# GCM_SCH.net
KiCad netlist of a schematic drawn in Altium Designer
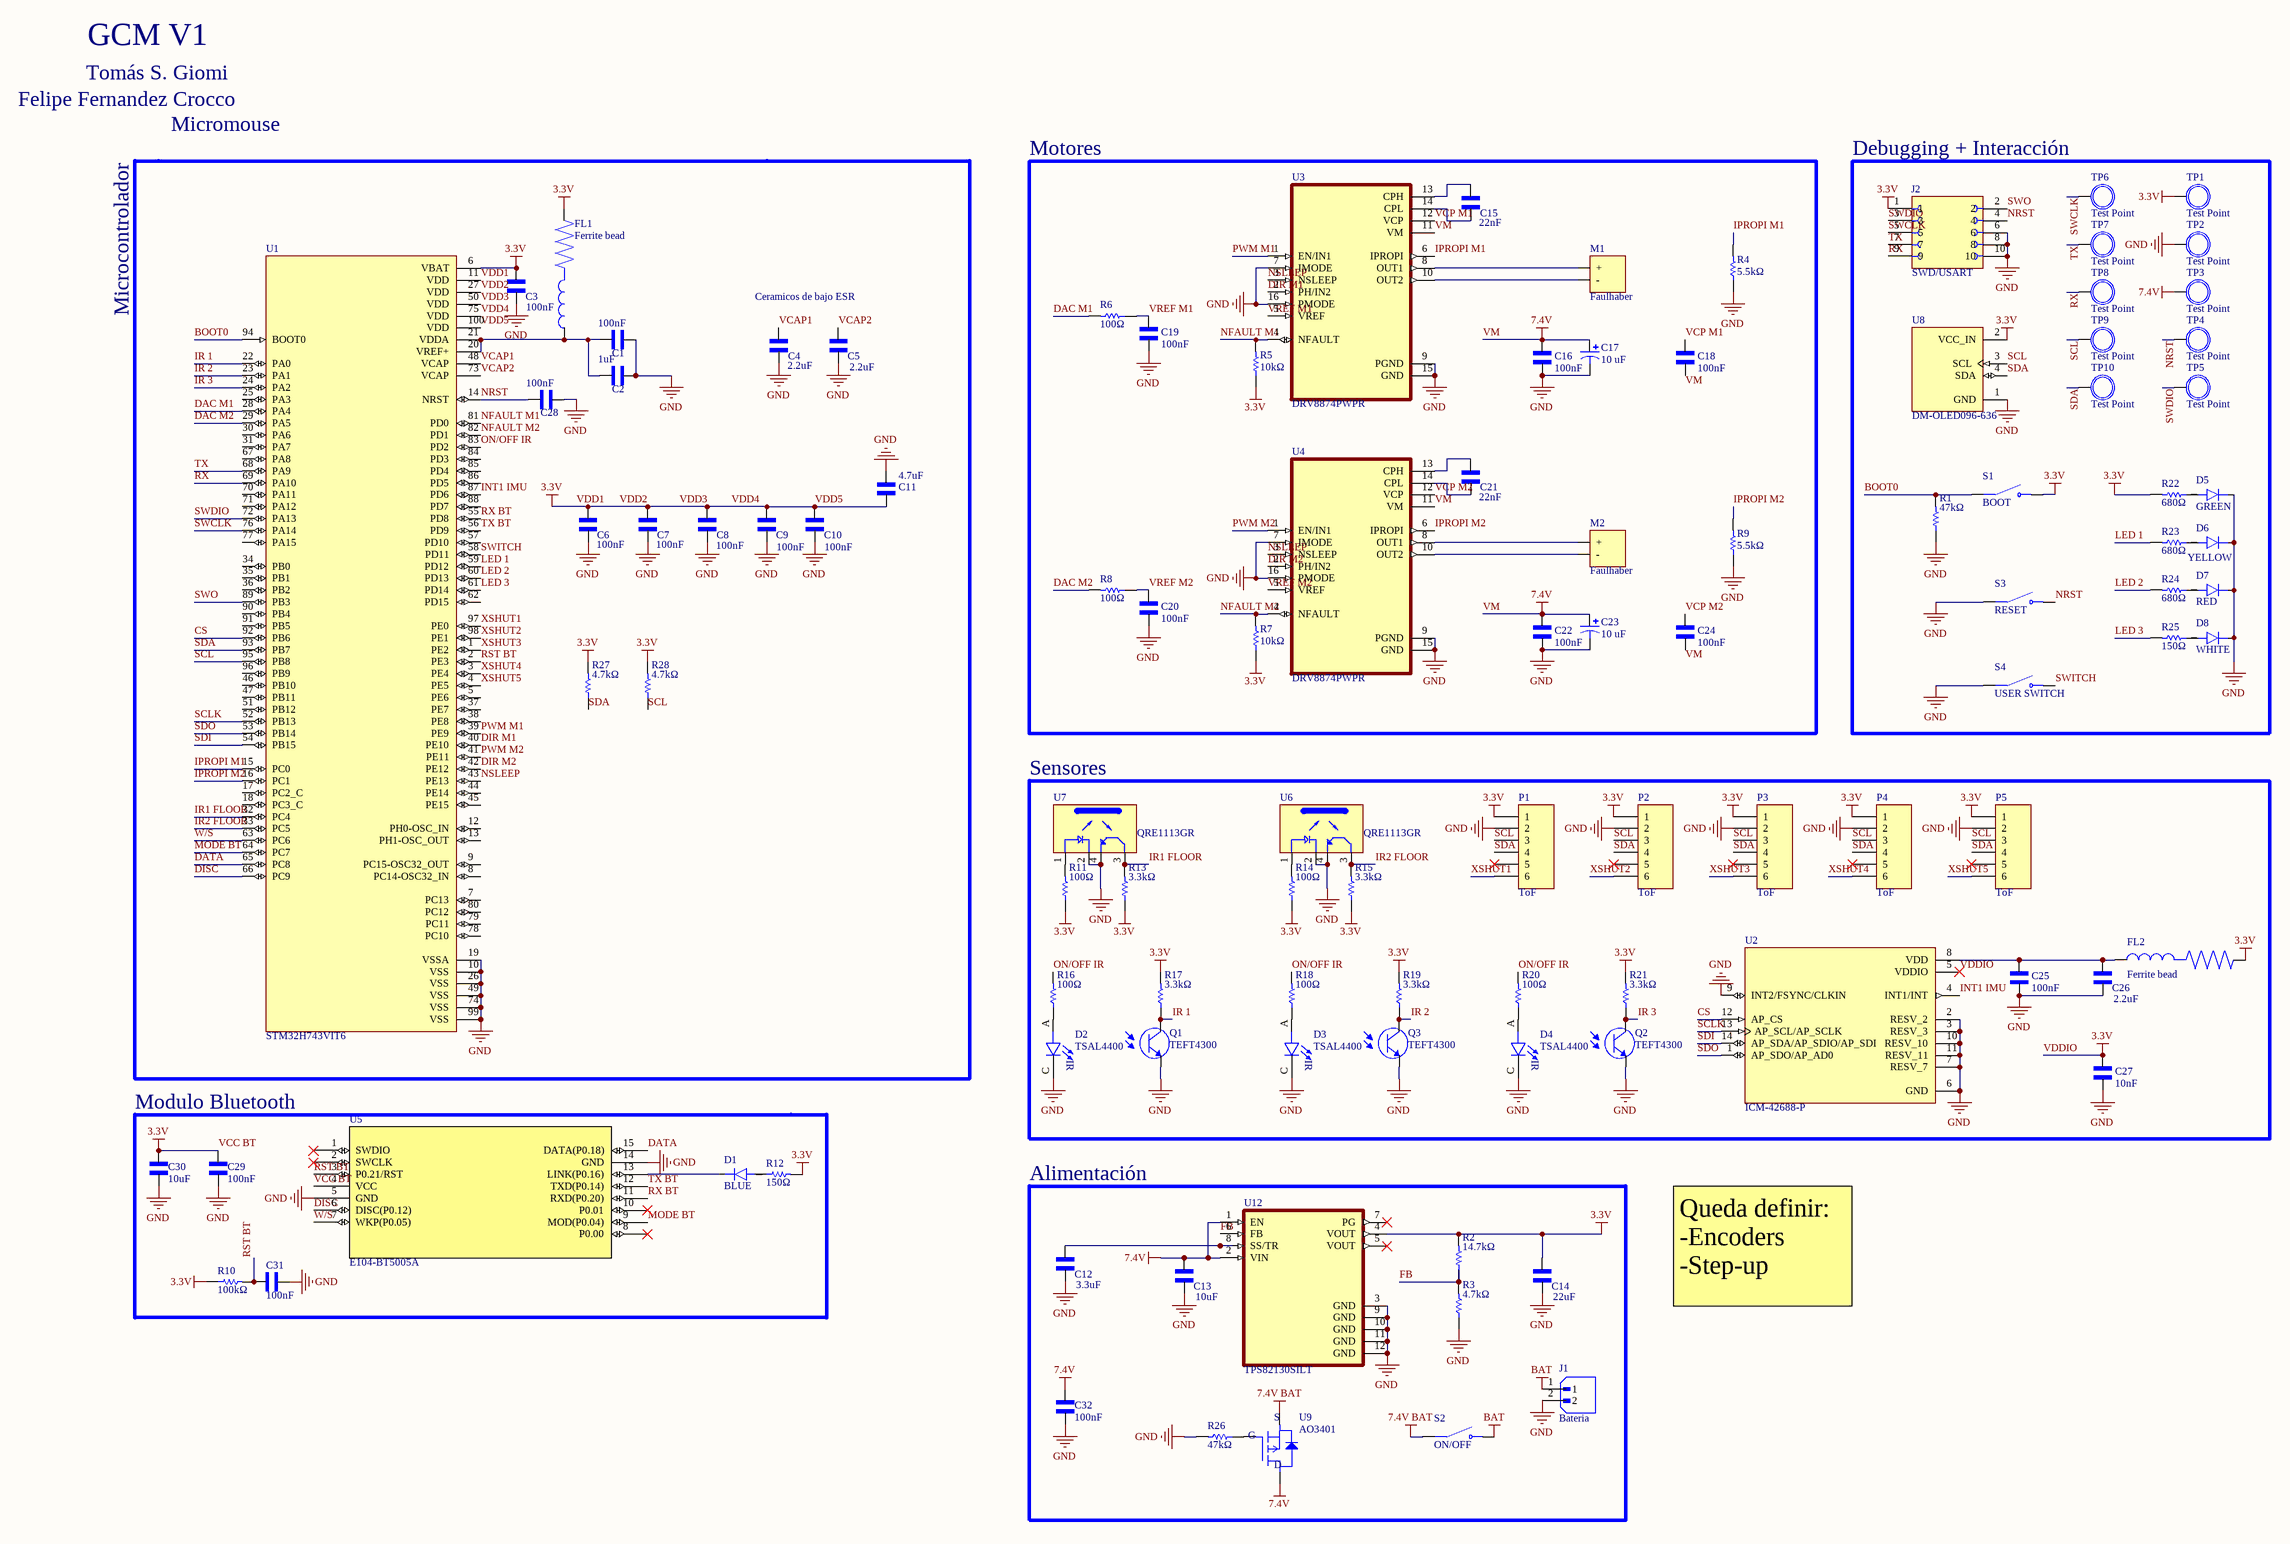
[diagram p0: GCM_SCH.SchDoc]

(export (version "E")
  (design (tool "Eeschema 10.0.6"))
  (components
    (comp (ref "C1")
      (value "100nF")
      (footprint "CAPACITOR TANTALIO")
      (description "0805")
      (fields (field (name "MP") "GRM035R60J475ME15D") (field (name "MF") "Murata"))
      (libsource (lib "") (part "CAPACITOR TANTALIO_1"))
    )
    (comp (ref "C2")
      (value "1uF")
      (footprint "CAPACITOR TANTALIO")
      (description "0805")
      (fields (field (name "MP") "GRM035R60J475ME15D") (field (name "MF") "Murata"))
      (libsource (lib "") (part "CAPACITOR TANTALIO_1"))
    )
    (comp (ref "C3")
      (value "100nF")
      (footprint "CAPACITOR TANTALIO")
      (description "0805")
      (fields (field (name "MP") "GRM035R60J475ME15D") (field (name "MF") "Murata"))
      (libsource (lib "GCMLibreriasSCH") (part "CAPACITOR TANTALIO"))
    )
    (comp (ref "C4")
      (value "2.2uF")
      (footprint "CAPACITOR TANTALIO")
      (description "0805")
      (fields (field (name "MP") "GRM035R60J475ME15D") (field (name "MF") "Murata"))
      (libsource (lib "GCMLibreriasSCH") (part "CAPACITOR TANTALIO"))
    )
    (comp (ref "C5")
      (value "2.2uF")
      (footprint "CAPACITOR TANTALIO")
      (description "0805")
      (fields (field (name "MP") "GRM035R60J475ME15D") (field (name "MF") "Murata"))
      (libsource (lib "GCMLibreriasSCH") (part "CAPACITOR TANTALIO"))
    )
    (comp (ref "C6")
      (value "100nF")
      (footprint "CAPACITOR TANTALIO")
      (description "0805")
      (fields (field (name "MP") "GRM035R60J475ME15D") (field (name "MF") "Murata"))
      (libsource (lib "GCMLibreriasSCH") (part "CAPACITOR TANTALIO"))
    )
    (comp (ref "C7")
      (value "100nF")
      (footprint "CAPACITOR TANTALIO")
      (description "0805")
      (fields (field (name "MP") "GRM035R60J475ME15D") (field (name "MF") "Murata"))
      (libsource (lib "GCMLibreriasSCH") (part "CAPACITOR TANTALIO"))
    )
    (comp (ref "C8")
      (value "100nF")
      (footprint "CAPACITOR TANTALIO")
      (description "0805")
      (fields (field (name "MP") "GRM035R60J475ME15D") (field (name "MF") "Murata"))
      (libsource (lib "GCMLibreriasSCH") (part "CAPACITOR TANTALIO"))
    )
    (comp (ref "C9")
      (value "100nF")
      (footprint "CAPACITOR TANTALIO")
      (description "0805")
      (fields (field (name "MP") "GRM035R60J475ME15D") (field (name "MF") "Murata"))
      (libsource (lib "GCMLibreriasSCH") (part "CAPACITOR TANTALIO"))
    )
    (comp (ref "C10")
      (value "100nF")
      (footprint "CAPACITOR TANTALIO")
      (description "0805")
      (fields (field (name "MP") "GRM035R60J475ME15D") (field (name "MF") "Murata"))
      (libsource (lib "GCMLibreriasSCH") (part "CAPACITOR TANTALIO"))
    )
    (comp (ref "C11")
      (value "4.7uF")
      (footprint "CAPACITOR TANTALIO")
      (description "0805")
      (fields (field (name "MP") "GRM035R60J475ME15D") (field (name "MF") "Murata"))
      (libsource (lib "GCMLibreriasSCH") (part "CAPACITOR TANTALIO"))
    )
    (comp (ref "C12")
      (value "3.3uF")
      (footprint "CAPACITOR TANTALIO")
      (description "0805")
      (fields (field (name "MP") "GRM035R60J475ME15D") (field (name "MF") "Murata"))
      (libsource (lib "GCMLibreriasSCH") (part "CAPACITOR TANTALIO"))
    )
    (comp (ref "C13")
      (value "10uF")
      (footprint "CAPACITOR TANTALIO")
      (description "0805")
      (fields (field (name "MP") "GRM035R60J475ME15D") (field (name "MF") "Murata"))
      (libsource (lib "GCMLibreriasSCH") (part "CAPACITOR TANTALIO"))
    )
    (comp (ref "C14")
      (value "22uF")
      (footprint "CAPACITOR TANTALIO")
      (description "0805")
      (fields (field (name "MP") "GRM035R60J475ME15D") (field (name "MF") "Murata"))
      (libsource (lib "GCMLibreriasSCH") (part "CAPACITOR TANTALIO"))
    )
    (comp (ref "C15")
      (value "22nF")
      (footprint "CAPACITOR TANTALIO")
      (description "0805")
      (fields (field (name "MP") "GRM035R60J475ME15D") (field (name "MF") "Murata"))
      (libsource (lib "GCMLibreriasSCH") (part "CAPACITOR TANTALIO"))
    )
    (comp (ref "C16")
      (value "100nF")
      (footprint "CAPACITOR TANTALIO")
      (description "0805")
      (fields (field (name "MP") "GRM035R60J475ME15D") (field (name "MF") "Murata"))
      (libsource (lib "GCMLibreriasSCH") (part "CAPACITOR TANTALIO"))
    )
    (comp (ref "C17")
      (value "10 uF")
      (footprint "Cap El 10uF")
      (libsource (lib "GCMLibreriasSCH") (part "Cap el 10 uF"))
    )
    (comp (ref "C18")
      (value "100nF")
      (footprint "CAPACITOR TANTALIO")
      (description "0805")
      (fields (field (name "MP") "GRM035R60J475ME15D") (field (name "MF") "Murata"))
      (libsource (lib "GCMLibreriasSCH") (part "CAPACITOR TANTALIO"))
    )
    (comp (ref "C19")
      (value "100nF")
      (footprint "CAPACITOR TANTALIO")
      (description "0805")
      (fields (field (name "MP") "GRM035R60J475ME15D") (field (name "MF") "Murata"))
      (libsource (lib "GCMLibreriasSCH") (part "CAPACITOR TANTALIO"))
    )
    (comp (ref "C20")
      (value "100nF")
      (footprint "CAPACITOR TANTALIO")
      (description "0805")
      (fields (field (name "MP") "GRM035R60J475ME15D") (field (name "MF") "Murata"))
      (libsource (lib "GCMLibreriasSCH") (part "CAPACITOR TANTALIO"))
    )
    (comp (ref "C21")
      (value "22nF")
      (footprint "CAPACITOR TANTALIO")
      (description "0805")
      (fields (field (name "MP") "GRM035R60J475ME15D") (field (name "MF") "Murata"))
      (libsource (lib "GCMLibreriasSCH") (part "CAPACITOR TANTALIO"))
    )
    (comp (ref "C22")
      (value "100nF")
      (footprint "CAPACITOR TANTALIO")
      (description "0805")
      (fields (field (name "MP") "GRM035R60J475ME15D") (field (name "MF") "Murata"))
      (libsource (lib "GCMLibreriasSCH") (part "CAPACITOR TANTALIO"))
    )
    (comp (ref "C23")
      (value "10 uF")
      (footprint "Cap El 10uF")
      (libsource (lib "GCMLibreriasSCH") (part "Cap el 10 uF"))
    )
    (comp (ref "C24")
      (value "100nF")
      (footprint "CAPACITOR TANTALIO")
      (description "0805")
      (fields (field (name "MP") "GRM035R60J475ME15D") (field (name "MF") "Murata"))
      (libsource (lib "GCMLibreriasSCH") (part "CAPACITOR TANTALIO"))
    )
    (comp (ref "C25")
      (value "100nF")
      (footprint "CAPACITOR TANTALIO")
      (description "0805")
      (fields (field (name "MP") "GRM035R60J475ME15D") (field (name "MF") "Murata"))
      (libsource (lib "GCMLibreriasSCH") (part "CAPACITOR TANTALIO"))
    )
    (comp (ref "C26")
      (value "2.2uF")
      (footprint "CAPACITOR TANTALIO")
      (description "0805")
      (fields (field (name "MP") "GRM035R60J475ME15D") (field (name "MF") "Murata"))
      (libsource (lib "GCMLibreriasSCH") (part "CAPACITOR TANTALIO"))
    )
    (comp (ref "C27")
      (value "10nF")
      (footprint "CAPACITOR TANTALIO")
      (description "0805")
      (fields (field (name "MP") "GRM035R60J475ME15D") (field (name "MF") "Murata"))
      (libsource (lib "GCMLibreriasSCH") (part "CAPACITOR TANTALIO"))
    )
    (comp (ref "C28")
      (value "100nF")
      (footprint "CAPACITOR TANTALIO")
      (description "0805")
      (fields (field (name "MP") "GRM035R60J475ME15D") (field (name "MF") "Murata"))
      (libsource (lib "") (part "CAPACITOR TANTALIO_1"))
    )
    (comp (ref "C29")
      (value "100nF")
      (footprint "CAPACITOR TANTALIO")
      (description "0805")
      (fields (field (name "MP") "GRM035R60J475ME15D") (field (name "MF") "Murata"))
      (libsource (lib "GCMLibreriasSCH") (part "CAPACITOR TANTALIO"))
    )
    (comp (ref "C30")
      (value "10uF")
      (footprint "CAPACITOR TANTALIO")
      (description "0805")
      (fields (field (name "MP") "GRM035R60J475ME15D") (field (name "MF") "Murata"))
      (libsource (lib "GCMLibreriasSCH") (part "CAPACITOR TANTALIO"))
    )
    (comp (ref "C31")
      (value "100nF")
      (footprint "CAPACITOR TANTALIO")
      (description "0805")
      (fields (field (name "MP") "GRM035R60J475ME15D") (field (name "MF") "Murata"))
      (libsource (lib "") (part "CAPACITOR TANTALIO_2"))
    )
    (comp (ref "C32")
      (value "100nF")
      (footprint "CAPACITOR TANTALIO")
      (description "0805")
      (fields (field (name "MP") "GRM035R60J475ME15D") (field (name "MF") "Murata"))
      (libsource (lib "GCMLibreriasSCH") (part "CAPACITOR TANTALIO"))
    )
    (comp (ref "D1")
      (value "BLUE")
      (footprint "LED SMD")
      (description "0805")
      (fields (field (name "MP") "597-5311-402F"))
      (libsource (lib "GCMLibreriasSCH") (part "LED SMD"))
    )
    (comp (ref "D2")
      (value "TSAL4400")
      (footprint "GCMLibreriasPCB:LEDRD254W45D335H610")
      (description "Infrared Emitter 940nm 36mW/sr Circular Top Mount 2-Pin T-1 Bulk")
      (fields (field (name "MF") "Vishay Semiconductor"))
      (libsource (lib "GCMLibreriasSCH") (part "TSAL4400"))
    )
    (comp (ref "D3")
      (value "TSAL4400")
      (footprint "GCMLibreriasPCB:LEDRD254W45D335H610")
      (description "Infrared Emitter 940nm 36mW/sr Circular Top Mount 2-Pin T-1 Bulk")
      (fields (field (name "MF") "Vishay Semiconductor"))
      (libsource (lib "GCMLibreriasSCH") (part "TSAL4400"))
    )
    (comp (ref "D4")
      (value "TSAL4400")
      (footprint "GCMLibreriasPCB:LEDRD254W45D335H610")
      (description "Infrared Emitter 940nm 36mW/sr Circular Top Mount 2-Pin T-1 Bulk")
      (fields (field (name "MF") "Vishay Semiconductor"))
      (libsource (lib "GCMLibreriasSCH") (part "TSAL4400"))
    )
    (comp (ref "D5")
      (value "GREEN")
      (footprint "LED SMD")
      (description "0805")
      (fields (field (name "MP") "597-5311-402F"))
      (libsource (lib "GCMLibreriasSCH") (part "LED SMD"))
    )
    (comp (ref "D6")
      (value "YELLOW")
      (footprint "LED SMD")
      (description "0805")
      (fields (field (name "MP") "597-5311-402F"))
      (libsource (lib "GCMLibreriasSCH") (part "LED SMD"))
    )
    (comp (ref "D7")
      (value "RED")
      (footprint "LED SMD")
      (description "0805")
      (fields (field (name "MP") "597-5311-402F"))
      (libsource (lib "GCMLibreriasSCH") (part "LED SMD"))
    )
    (comp (ref "D8")
      (value "WHITE")
      (footprint "LED SMD")
      (description "0805")
      (fields (field (name "MP") "597-5311-402F"))
      (libsource (lib "GCMLibreriasSCH") (part "LED SMD"))
    )
    (comp (ref "FL1")
      (value "Ferrite bead")
      (footprint "BEADC1608X95N")
      (description "600 Ohms @ 100 MHz 1 - Ferrite Bead 0603 (1608 Metric) 500mA 380mOhm")
      (fields (field (name "MF") "Murata") (field (name "MP") "BLM18AG601SN1D"))
      (libsource (lib "GCMLibreriasSCH") (part "BLM18AG601SN1D"))
    )
    (comp (ref "FL2")
      (value "Ferrite bead")
      (footprint "BEADC1608X95N")
      (description "600 Ohms @ 100 MHz 1 - Ferrite Bead 0603 (1608 Metric) 500mA 380mOhm")
      (fields (field (name "MF") "Murata") (field (name "MP") "BLM18AG601SN1D"))
      (libsource (lib "GCMLibreriasSCH") (part "BLM18AG601SN1D"))
    )
    (comp (ref "J1")
      (value "Bateria")
      (footprint "JST_B2B-XH-A")
      (fields
        (field (name "MF") "{'manufacturer': u'JST Sales America Inc.'}")
        (field (name "MP") "B2B-XH-A")
      )
      (libsource (lib "GCMLibreriasSCH") (part "B2B-XH-A"))
    )
    (comp (ref "J2")
      (value "SWD/USART")
      (footprint "AMPHENOL_20021311-00026T4LF")
      (fields (field (name "MF") "Amphenol ICC") (field (name "MP") "20021311-00026T4LF"))
      (libsource (lib "GCMLibreriasSCH") (part "20021311-00026T4LF"))
    )
    (comp (ref "M1")
      (value "Faulhaber")
      (footprint "MOTOR")
      (fields (field (name "PUBLISHER") "Altium Limited"))
      (libsource (lib "GCMLibreriasSCH") (part "Faulhaber"))
    )
    (comp (ref "M2")
      (value "Faulhaber")
      (footprint "MOTOR")
      (fields (field (name "PUBLISHER") "Altium Limited"))
      (libsource (lib "GCMLibreriasSCH") (part "Faulhaber"))
    )
    (comp (ref "P1")
      (value "ToF")
      (footprint "FHDR1X6")
      (fields (field (name "PUBLISHER") "Altium Limited"))
      (libsource (lib "GCMLibreriasSCH") (part "FHeader 6X1"))
    )
    (comp (ref "P2")
      (value "ToF")
      (footprint "FHDR1X6")
      (fields (field (name "PUBLISHER") "Altium Limited"))
      (libsource (lib "GCMLibreriasSCH") (part "FHeader 6X1"))
    )
    (comp (ref "P3")
      (value "ToF")
      (footprint "FHDR1X6")
      (fields (field (name "PUBLISHER") "Altium Limited"))
      (libsource (lib "GCMLibreriasSCH") (part "FHeader 6X1"))
    )
    (comp (ref "P4")
      (value "ToF")
      (footprint "FHDR1X6")
      (fields (field (name "PUBLISHER") "Altium Limited"))
      (libsource (lib "GCMLibreriasSCH") (part "FHeader 6X1"))
    )
    (comp (ref "P5")
      (value "ToF")
      (footprint "FHDR1X6")
      (fields (field (name "PUBLISHER") "Altium Limited"))
      (libsource (lib "GCMLibreriasSCH") (part "FHeader 6X1"))
    )
    (comp (ref "Q1")
      (value "TEFT4300")
      (footprint "XDCR_TEFT4300")
      (description "Phototransistors 925nm Top View Radial, 3mm Dia (T-1)")
      (fields (field (name "MF") "Vishay Semiconductor"))
      (libsource (lib "GCMLibreriasSCH") (part "TEFT4300"))
    )
    (comp (ref "Q2")
      (value "TEFT4300")
      (footprint "XDCR_TEFT4300")
      (description "Phototransistors 925nm Top View Radial, 3mm Dia (T-1)")
      (fields (field (name "MF") "Vishay Semiconductor"))
      (libsource (lib "GCMLibreriasSCH") (part "TEFT4300"))
    )
    (comp (ref "Q3")
      (value "TEFT4300")
      (footprint "XDCR_TEFT4300")
      (description "Phototransistors 925nm Top View Radial, 3mm Dia (T-1)")
      (fields (field (name "MF") "Vishay Semiconductor"))
      (libsource (lib "GCMLibreriasSCH") (part "TEFT4300"))
    )
    (comp (ref "R1")
      (value "47kΩ")
      (footprint "RESISTENCIA SMD")
      (description "0805")
      (fields (field (name "PUBLISHER") "Altium Limited"))
      (libsource (lib "GCMLibreriasSCH") (part "RESISTENCIA"))
    )
    (comp (ref "R2")
      (value "14.7kΩ")
      (footprint "RESISTENCIA SMD")
      (description "0805")
      (fields (field (name "PUBLISHER") "Altium Limited"))
      (libsource (lib "GCMLibreriasSCH") (part "RESISTENCIA"))
    )
    (comp (ref "R3")
      (value "4.7kΩ")
      (footprint "RESISTENCIA SMD")
      (description "0805")
      (fields (field (name "PUBLISHER") "Altium Limited"))
      (libsource (lib "GCMLibreriasSCH") (part "RESISTENCIA"))
    )
    (comp (ref "R4")
      (value "5.5kΩ")
      (footprint "RESISTENCIA SMD")
      (description "0805")
      (fields (field (name "PUBLISHER") "Altium Limited"))
      (libsource (lib "GCMLibreriasSCH") (part "RESISTENCIA"))
    )
    (comp (ref "R5")
      (value "10kΩ")
      (footprint "RESISTENCIA SMD")
      (description "0805")
      (fields (field (name "PUBLISHER") "Altium Limited"))
      (libsource (lib "GCMLibreriasSCH") (part "RESISTENCIA"))
    )
    (comp (ref "R6")
      (value "100Ω")
      (footprint "RESISTENCIA SMD")
      (description "0805")
      (fields (field (name "PUBLISHER") "Altium Limited"))
      (libsource (lib "GCMLibreriasSCH") (part "RESISTENCIA"))
    )
    (comp (ref "R7")
      (value "10kΩ")
      (footprint "RESISTENCIA SMD")
      (description "0805")
      (fields (field (name "PUBLISHER") "Altium Limited"))
      (libsource (lib "GCMLibreriasSCH") (part "RESISTENCIA"))
    )
    (comp (ref "R8")
      (value "100Ω")
      (footprint "RESISTENCIA SMD")
      (description "0805")
      (fields (field (name "PUBLISHER") "Altium Limited"))
      (libsource (lib "GCMLibreriasSCH") (part "RESISTENCIA"))
    )
    (comp (ref "R9")
      (value "5.5kΩ")
      (footprint "RESISTENCIA SMD")
      (description "0805")
      (fields (field (name "PUBLISHER") "Altium Limited"))
      (libsource (lib "GCMLibreriasSCH") (part "RESISTENCIA"))
    )
    (comp (ref "R10")
      (value "100kΩ")
      (footprint "RESISTENCIA SMD")
      (description "0805")
      (fields (field (name "PUBLISHER") "Altium Limited"))
      (libsource (lib "GCMLibreriasSCH") (part "RESISTENCIA"))
    )
    (comp (ref "R11")
      (value "100Ω")
      (footprint "RESISTENCIA SMD")
      (description "0805")
      (fields (field (name "PUBLISHER") "Altium Limited"))
      (libsource (lib "GCMLibreriasSCH") (part "RESISTENCIA"))
    )
    (comp (ref "R12")
      (value "150Ω")
      (footprint "RESISTENCIA SMD")
      (description "0805")
      (fields (field (name "PUBLISHER") "Altium Limited"))
      (libsource (lib "GCMLibreriasSCH") (part "RESISTENCIA"))
    )
    (comp (ref "R13")
      (value "3.3kΩ")
      (footprint "RESISTENCIA SMD")
      (description "0805")
      (fields (field (name "PUBLISHER") "Altium Limited"))
      (libsource (lib "GCMLibreriasSCH") (part "RESISTENCIA"))
    )
    (comp (ref "R14")
      (value "100Ω")
      (footprint "RESISTENCIA SMD")
      (description "0805")
      (fields (field (name "PUBLISHER") "Altium Limited"))
      (libsource (lib "GCMLibreriasSCH") (part "RESISTENCIA"))
    )
    (comp (ref "R15")
      (value "3.3kΩ")
      (footprint "RESISTENCIA SMD")
      (description "0805")
      (fields (field (name "PUBLISHER") "Altium Limited"))
      (libsource (lib "GCMLibreriasSCH") (part "RESISTENCIA"))
    )
    (comp (ref "R16")
      (value "100Ω")
      (footprint "RESISTENCIA SMD")
      (description "0805")
      (fields (field (name "PUBLISHER") "Altium Limited"))
      (libsource (lib "GCMLibreriasSCH") (part "RESISTENCIA"))
    )
    (comp (ref "R17")
      (value "3.3kΩ")
      (footprint "RESISTENCIA SMD")
      (description "0805")
      (fields (field (name "PUBLISHER") "Altium Limited"))
      (libsource (lib "GCMLibreriasSCH") (part "RESISTENCIA"))
    )
    (comp (ref "R18")
      (value "100Ω")
      (footprint "RESISTENCIA SMD")
      (description "0805")
      (fields (field (name "PUBLISHER") "Altium Limited"))
      (libsource (lib "GCMLibreriasSCH") (part "RESISTENCIA"))
    )
    (comp (ref "R19")
      (value "3.3kΩ")
      (footprint "RESISTENCIA SMD")
      (description "0805")
      (fields (field (name "PUBLISHER") "Altium Limited"))
      (libsource (lib "GCMLibreriasSCH") (part "RESISTENCIA"))
    )
    (comp (ref "R20")
      (value "100Ω")
      (footprint "RESISTENCIA SMD")
      (description "0805")
      (fields (field (name "PUBLISHER") "Altium Limited"))
      (libsource (lib "GCMLibreriasSCH") (part "RESISTENCIA"))
    )
    (comp (ref "R21")
      (value "3.3kΩ")
      (footprint "RESISTENCIA SMD")
      (description "0805")
      (fields (field (name "PUBLISHER") "Altium Limited"))
      (libsource (lib "GCMLibreriasSCH") (part "RESISTENCIA"))
    )
    (comp (ref "R22")
      (value "680Ω")
      (footprint "RESISTENCIA SMD")
      (description "0805")
      (fields (field (name "PUBLISHER") "Altium Limited"))
      (libsource (lib "GCMLibreriasSCH") (part "RESISTENCIA"))
    )
    (comp (ref "R23")
      (value "680Ω")
      (footprint "RESISTENCIA SMD")
      (description "0805")
      (fields (field (name "PUBLISHER") "Altium Limited"))
      (libsource (lib "GCMLibreriasSCH") (part "RESISTENCIA"))
    )
    (comp (ref "R24")
      (value "680Ω")
      (footprint "RESISTENCIA SMD")
      (description "0805")
      (fields (field (name "PUBLISHER") "Altium Limited"))
      (libsource (lib "GCMLibreriasSCH") (part "RESISTENCIA"))
    )
    (comp (ref "R25")
      (value "150Ω")
      (footprint "RESISTENCIA SMD")
      (description "0805")
      (fields (field (name "PUBLISHER") "Altium Limited"))
      (libsource (lib "GCMLibreriasSCH") (part "RESISTENCIA"))
    )
    (comp (ref "R26")
      (value "47kΩ")
      (footprint "RESISTENCIA SMD")
      (description "0805")
      (fields (field (name "PUBLISHER") "Altium Limited"))
      (libsource (lib "GCMLibreriasSCH") (part "RESISTENCIA"))
    )
    (comp (ref "R27")
      (value "4.7kΩ")
      (footprint "RESISTENCIA SMD")
      (description "0805")
      (fields (field (name "PUBLISHER") "Altium Limited"))
      (libsource (lib "GCMLibreriasSCH") (part "RESISTENCIA"))
    )
    (comp (ref "R28")
      (value "4.7kΩ")
      (footprint "RESISTENCIA SMD")
      (description "0805")
      (fields (field (name "PUBLISHER") "Altium Limited"))
      (libsource (lib "GCMLibreriasSCH") (part "RESISTENCIA"))
    )
    (comp (ref "S1")
      (value "BOOT")
      (footprint "SW_TS09-63-25-WT-160-SMT-TR")
      (description "6.1 x 3.7 mm, 2.5 mm Actuator Height, 160 gf, White, Surface Mount, SPST, Tactile Switch")
      (fields (field (name "MF") "Same Sky") (field (name "MP") "TS09-63-25-WT-160-SMT-TR"))
      (libsource (lib "GCMLibreriasSCH") (part "TS09-63-25-WT-160-SMT-TR"))
    )
    (comp (ref "S2")
      (value "ON/OFF")
      (footprint "SW_L101011ML04Q")
      (description "Switch Slide ON OFF SPST Side Slide 4A 250VAC 125VDC PC Pins Thru-Hole Bulk")
      (fields (field (name "MF") "C&K") (field (name "MP") "L101011ML04Q"))
      (libsource (lib "GCMLibreriasSCH") (part "L101011ML04Q"))
    )
    (comp (ref "S3")
      (value "RESET")
      (footprint "SW_TS09-63-25-WT-160-SMT-TR")
      (description "6.1 x 3.7 mm, 2.5 mm Actuator Height, 160 gf, White, Surface Mount, SPST, Tactile Switch")
      (fields (field (name "MF") "Same Sky") (field (name "MP") "TS09-63-25-WT-160-SMT-TR"))
      (libsource (lib "GCMLibreriasSCH") (part "TS09-63-25-WT-160-SMT-TR"))
    )
    (comp (ref "S4")
      (value "USER SWITCH")
      (footprint "SW_TS09-63-25-WT-160-SMT-TR")
      (description "6.1 x 3.7 mm, 2.5 mm Actuator Height, 160 gf, White, Surface Mount, SPST, Tactile Switch")
      (fields (field (name "MF") "Same Sky") (field (name "MP") "TS09-63-25-WT-160-SMT-TR"))
      (libsource (lib "GCMLibreriasSCH") (part "TS09-63-25-WT-160-SMT-TR"))
    )
    (comp (ref "TP1")
      (value "Test Point")
      (footprint "TestPoint")
      (libsource (lib "GCMLibreriasSCH") (part "Test Point"))
    )
    (comp (ref "TP2")
      (value "Test Point")
      (footprint "TestPoint")
      (libsource (lib "GCMLibreriasSCH") (part "Test Point"))
    )
    (comp (ref "TP3")
      (value "Test Point")
      (footprint "TestPoint")
      (libsource (lib "GCMLibreriasSCH") (part "Test Point"))
    )
    (comp (ref "TP4")
      (value "Test Point")
      (footprint "TestPoint")
      (libsource (lib "GCMLibreriasSCH") (part "Test Point"))
    )
    (comp (ref "TP5")
      (value "Test Point")
      (footprint "TestPoint")
      (libsource (lib "GCMLibreriasSCH") (part "Test Point"))
    )
    (comp (ref "TP6")
      (value "Test Point")
      (footprint "TestPoint")
      (libsource (lib "GCMLibreriasSCH") (part "Test Point"))
    )
    (comp (ref "TP7")
      (value "Test Point")
      (footprint "TestPoint")
      (libsource (lib "GCMLibreriasSCH") (part "Test Point"))
    )
    (comp (ref "TP8")
      (value "Test Point")
      (footprint "TestPoint")
      (libsource (lib "GCMLibreriasSCH") (part "Test Point"))
    )
    (comp (ref "TP9")
      (value "Test Point")
      (footprint "TestPoint")
      (libsource (lib "GCMLibreriasSCH") (part "Test Point"))
    )
    (comp (ref "TP10")
      (value "Test Point")
      (footprint "TestPoint")
      (libsource (lib "GCMLibreriasSCH") (part "Test Point"))
    )
    (comp (ref "U1")
      (value "STM32H743VIT6")
      (footprint "QFP50P1600X1600X160-100N")
      (fields (field (name "MF") "STMicroelectronics"))
      (libsource (lib "GCMLibreriasSCH") (part "STM32H743VIT6"))
    )
    (comp (ref "U2")
      (value "ICM-42688-P")
      (footprint "PQFN50P300X250X97-14N")
      (description "Accelerometer, Gyroscope, 6 Axis Sensor Output")
      (libsource (lib "GCMLibreriasSCH") (part "ICM-42688-P"))
    )
    (comp (ref "U3")
      (value "DRV8874PWPR")
      (footprint "SOP65P640X120-17N")
      (description "40-V, 6-A H-bridge motor driver with integrated current sensing feedback")
      (fields (field (name "MF") "Texas Instruments"))
      (libsource (lib "GCMLibreriasSCH") (part "DRV8874PWPR"))
    )
    (comp (ref "U4")
      (value "DRV8874PWPR")
      (footprint "SOP65P640X120-17N")
      (description "40-V, 6-A H-bridge motor driver with integrated current sensing feedback")
      (fields (field (name "MF") "Texas Instruments"))
      (libsource (lib "GCMLibreriasSCH") (part "DRV8874PWPR"))
    )
    (comp (ref "U5")
      (value "E104-BT5005A")
      (footprint "MOD15_E104-BT5005A_BYT")
      (description "No Description Available")
      (fields (field (name "COPYRIGHT") "Copyright (C) 2026 Ultra Librarian. All rights reserved."))
      (libsource (lib "GCMLibreriasSCH") (part "E104-BT5005A"))
    )
    (comp (ref "U6")
      (value "QRE1113GR")
      (footprint "SOIC180P460X187-4N")
      (description "Reflective Optical Sensor 0.039 (1mm) 4-SMD, Gull Wing")
      (fields (field (name "MF") "ON Semiconductor"))
      (libsource (lib "GCMLibreriasSCH") (part "QRE1113GR"))
    )
    (comp (ref "U7")
      (value "QRE1113GR")
      (footprint "SOIC180P460X187-4N")
      (description "Reflective Optical Sensor 0.039 (1mm) 4-SMD, Gull Wing")
      (fields (field (name "MF") "ON Semiconductor"))
      (libsource (lib "GCMLibreriasSCH") (part "QRE1113GR"))
    )
    (comp (ref "U8")
      (value "DM-OLED096-636")
      (footprint "MODULE_DM-OLED096-636")
      (description "0.96â€ 128 X 64 MONOCHROME GRAPHIC OLED DISPLAY MODULE - I2C")
      (fields (field (name "MF") "Display Module"))
      (libsource (lib "GCMLibreriasSCH") (part "DM-OLED096-636"))
    )
    (comp (ref "U9")
      (value "AO3401")
      (footprint "SOT23")
      (description "P-Channel 30 V 4A (Ta) 1.4W (Ta) Surface Mount SOT-23-3")
      (fields (field (name "MF") "Alpha & Omega Semiconductor"))
      (libsource (lib "GCMLibreriasSCH") (part "AO3401"))
    )
    (comp (ref "U12")
      (value "TPS82130SILT")
      (footprint "CONV_TPS82140SILR")
      (description "Non-Isolated PoL Module DC DC Converter 1 Output 0.9 ~ 5V - - - 3A 3V - 17V Input")
      (fields (field (name "MF") "Texas Instruments") (field (name "MP") "TPS82130SIL"))
      (libsource (lib "GCMLibreriasSCH") (part "TPS82130SILT"))
    )
  )
  (nets
    (net (code "1") (name "/BOOT0") (class "Default")
      (node (ref "R1") (pin "2") (pinfunction "2_2") (pintype "passive"))
      (node (ref "S1") (pin "1") (pinfunction "1_1") (pintype "passive"))
      (node (ref "U1") (pin "94") (pinfunction "BOOT0_94") (pintype "input"))
    )
    (net (code "2") (name "/CS") (class "Default")
      (node (ref "U1") (pin "92") (pinfunction "PB6_92") (pintype "bidirectional"))
      (node (ref "U2") (pin "12") (pinfunction "AP_CS_12") (pintype "input"))
    )
    (net (code "3") (name "/DAC M1") (class "Default")
      (node (ref "R6") (pin "2") (pinfunction "2_2") (pintype "passive"))
      (node (ref "U1") (pin "28") (pinfunction "PA4_28") (pintype "bidirectional"))
    )
    (net (code "4") (name "/DAC M2") (class "Default")
      (node (ref "R8") (pin "2") (pinfunction "2_2") (pintype "passive"))
      (node (ref "U1") (pin "29") (pinfunction "PA5_29") (pintype "bidirectional"))
    )
    (net (code "5") (name "/DATA") (class "Default")
      (node (ref "U1") (pin "65") (pinfunction "PC8_65") (pintype "bidirectional"))
      (node (ref "U5") (pin "15") (pinfunction "DATA(P0.18)_15") (pintype "bidirectional"))
    )
    (net (code "6") (name "/DIR M1") (class "Default")
      (node (ref "U1") (pin "40") (pinfunction "PE10_40") (pintype "bidirectional"))
      (node (ref "U3") (pin "2") (pinfunction "PH/IN2_2") (pintype "input"))
    )
    (net (code "7") (name "/DIR M2") (class "Default")
      (node (ref "U1") (pin "42") (pinfunction "PE12_42") (pintype "bidirectional"))
      (node (ref "U4") (pin "2") (pinfunction "PH/IN2_2") (pintype "input"))
    )
    (net (code "8") (name "/DISC") (class "Default")
      (node (ref "U1") (pin "66") (pinfunction "PC9_66") (pintype "bidirectional"))
      (node (ref "U5") (pin "6") (pinfunction "DISC(P0.12)_6") (pintype "bidirectional"))
    )
    (net (code "9") (name "/FB") (class "Default")
      (node (ref "R2") (pin "1") (pinfunction "1_1") (pintype "passive"))
      (node (ref "R3") (pin "2") (pinfunction "2_2") (pintype "passive"))
      (node (ref "U12") (pin "6") (pinfunction "FB_6") (pintype "input"))
    )
    (net (code "10") (name "/INT1 IMU") (class "Default")
      (node (ref "U1") (pin "87") (pinfunction "PD6_87") (pintype "bidirectional"))
      (node (ref "U2") (pin "4") (pinfunction "INT1/INT_4") (pintype "output"))
    )
    (net (code "11") (name "/IPROPI M1") (class "Default")
      (node (ref "R4") (pin "2") (pinfunction "2_2") (pintype "passive"))
      (node (ref "U1") (pin "15") (pinfunction "PC0_15") (pintype "bidirectional"))
      (node (ref "U3") (pin "6") (pinfunction "IPROPI_6") (pintype "output"))
    )
    (net (code "12") (name "/IPROPI M2") (class "Default")
      (node (ref "R9") (pin "2") (pinfunction "2_2") (pintype "passive"))
      (node (ref "U1") (pin "16") (pinfunction "PC1_16") (pintype "bidirectional"))
      (node (ref "U4") (pin "6") (pinfunction "IPROPI_6") (pintype "output"))
    )
    (net (code "13") (name "/IR 1") (class "Default")
      (node (ref "Q1") (pin "C") (pinfunction "C_C") (pintype "passive"))
      (node (ref "R17") (pin "1") (pinfunction "1_1") (pintype "passive"))
      (node (ref "U1") (pin "22") (pinfunction "PA0_22") (pintype "bidirectional"))
    )
    (net (code "14") (name "/IR 2") (class "Default")
      (node (ref "Q3") (pin "C") (pinfunction "C_C") (pintype "passive"))
      (node (ref "R19") (pin "1") (pinfunction "1_1") (pintype "passive"))
      (node (ref "U1") (pin "23") (pinfunction "PA1_23") (pintype "bidirectional"))
    )
    (net (code "15") (name "/IR 3") (class "Default")
      (node (ref "Q2") (pin "C") (pinfunction "C_C") (pintype "passive"))
      (node (ref "R21") (pin "1") (pinfunction "1_1") (pintype "passive"))
      (node (ref "U1") (pin "24") (pinfunction "PA2_24") (pintype "bidirectional"))
    )
    (net (code "16") (name "/IR1 FLOOR") (class "Default")
      (node (ref "R13") (pin "2") (pinfunction "2_2") (pintype "passive"))
      (node (ref "U1") (pin "32") (pinfunction "PC4_32") (pintype "bidirectional"))
      (node (ref "U7") (pin "3") (pinfunction "CT_3") (pintype "passive"))
    )
    (net (code "17") (name "/IR2 FLOOR") (class "Default")
      (node (ref "R15") (pin "2") (pinfunction "2_2") (pintype "passive"))
      (node (ref "U1") (pin "33") (pinfunction "PC5_33") (pintype "bidirectional"))
      (node (ref "U6") (pin "3") (pinfunction "CT_3") (pintype "passive"))
    )
    (net (code "18") (name "/LED 1") (class "Default")
      (node (ref "R23") (pin "2") (pinfunction "2_2") (pintype "passive"))
      (node (ref "U1") (pin "59") (pinfunction "PD12_59") (pintype "bidirectional"))
    )
    (net (code "19") (name "/LED 2") (class "Default")
      (node (ref "R24") (pin "2") (pinfunction "2_2") (pintype "passive"))
      (node (ref "U1") (pin "60") (pinfunction "PD13_60") (pintype "bidirectional"))
    )
    (net (code "20") (name "/LED 3") (class "Default")
      (node (ref "R25") (pin "2") (pinfunction "2_2") (pintype "passive"))
      (node (ref "U1") (pin "61") (pinfunction "PD14_61") (pintype "bidirectional"))
    )
    (net (code "21") (name "/MODE BT") (class "Default")
      (node (ref "U1") (pin "64") (pinfunction "PC7_64") (pintype "bidirectional"))
      (node (ref "U5") (pin "9") (pinfunction "MOD(P0.04)_9") (pintype "bidirectional"))
    )
    (net (code "22") (name "/NFAULT M1") (class "Default")
      (node (ref "R5") (pin "2") (pinfunction "2_2") (pintype "passive"))
      (node (ref "U1") (pin "81") (pinfunction "PD0_81") (pintype "bidirectional"))
      (node (ref "U3") (pin "4") (pinfunction "NFAULT_4") (pintype "bidirectional"))
    )
    (net (code "23") (name "/NFAULT M2") (class "Default")
      (node (ref "R7") (pin "2") (pinfunction "2_2") (pintype "passive"))
      (node (ref "U1") (pin "82") (pinfunction "PD1_82") (pintype "bidirectional"))
      (node (ref "U4") (pin "4") (pinfunction "NFAULT_4") (pintype "bidirectional"))
    )
    (net (code "24") (name "/NRST") (class "Default")
      (node (ref "C28") (pin "1") (pinfunction "1_1") (pintype "passive"))
      (node (ref "J2") (pin "4") (pinfunction "4_4") (pintype "passive"))
      (node (ref "S3") (pin "2") (pinfunction "2_2") (pintype "passive"))
      (node (ref "TP4") (pin "1") (pinfunction "1_1") (pintype "passive"))
      (node (ref "U1") (pin "14") (pinfunction "NRST_14") (pintype "bidirectional"))
    )
    (net (code "25") (name "/NSLEEP") (class "Default")
      (node (ref "U1") (pin "43") (pinfunction "PE13_43") (pintype "bidirectional"))
      (node (ref "U3") (pin "3") (pinfunction "NSLEEP_3") (pintype "input"))
      (node (ref "U4") (pin "3") (pinfunction "NSLEEP_3") (pintype "input"))
    )
    (net (code "26") (name "/ON{slash}OFF IR") (class "Default")
      (node (ref "R16") (pin "2") (pinfunction "2_2") (pintype "passive"))
      (node (ref "R18") (pin "2") (pinfunction "2_2") (pintype "passive"))
      (node (ref "R20") (pin "2") (pinfunction "2_2") (pintype "passive"))
      (node (ref "U1") (pin "83") (pinfunction "PD2_83") (pintype "bidirectional"))
    )
    (net (code "27") (name "/PWM M1") (class "Default")
      (node (ref "U1") (pin "39") (pinfunction "PE9_39") (pintype "bidirectional"))
      (node (ref "U3") (pin "1") (pinfunction "EN/IN1_1") (pintype "input"))
    )
    (net (code "28") (name "/PWM M2") (class "Default")
      (node (ref "U1") (pin "41") (pinfunction "PE11_41") (pintype "bidirectional"))
      (node (ref "U4") (pin "1") (pinfunction "EN/IN1_1") (pintype "input"))
    )
    (net (code "29") (name "/RST BT") (class "Default")
      (node (ref "C31") (pin "2") (pinfunction "2_2") (pintype "passive"))
      (node (ref "R10") (pin "2") (pinfunction "2_2") (pintype "passive"))
      (node (ref "U1") (pin "2") (pinfunction "PE3_2") (pintype "bidirectional"))
      (node (ref "U5") (pin "3") (pinfunction "P0.21/RST_3") (pintype "bidirectional"))
    )
    (net (code "30") (name "/RX") (class "Default")
      (node (ref "J2") (pin "9") (pinfunction "9_9") (pintype "passive"))
      (node (ref "TP8") (pin "1") (pinfunction "1_1") (pintype "passive"))
      (node (ref "U1") (pin "69") (pinfunction "PA10_69") (pintype "bidirectional"))
    )
    (net (code "31") (name "/RX BT") (class "Default")
      (node (ref "U1") (pin "55") (pinfunction "PD8_55") (pintype "bidirectional"))
      (node (ref "U5") (pin "11") (pinfunction "RXD(P0.20)_11") (pintype "bidirectional"))
    )
    (net (code "32") (name "/SCL") (class "Default")
      (node (ref "P1") (pin "3") (pinfunction "3_3") (pintype "passive"))
      (node (ref "P2") (pin "3") (pinfunction "3_3") (pintype "passive"))
      (node (ref "P3") (pin "3") (pinfunction "3_3") (pintype "passive"))
      (node (ref "P4") (pin "3") (pinfunction "3_3") (pintype "passive"))
      (node (ref "P5") (pin "3") (pinfunction "3_3") (pintype "passive"))
      (node (ref "R28") (pin "1") (pinfunction "1_1") (pintype "passive"))
      (node (ref "TP9") (pin "1") (pinfunction "1_1") (pintype "passive"))
      (node (ref "U1") (pin "95") (pinfunction "PB8_95") (pintype "bidirectional"))
      (node (ref "U8") (pin "3") (pinfunction "SCL_3") (pintype "input"))
    )
    (net (code "33") (name "/SCLK") (class "Default")
      (node (ref "U1") (pin "52") (pinfunction "PB13_52") (pintype "bidirectional"))
      (node (ref "U2") (pin "13") (pinfunction "AP_SCL/AP_SCLK_13") (pintype "input"))
    )
    (net (code "34") (name "/SDA") (class "Default")
      (node (ref "P1") (pin "4") (pinfunction "4_4") (pintype "passive"))
      (node (ref "P2") (pin "4") (pinfunction "4_4") (pintype "passive"))
      (node (ref "P3") (pin "4") (pinfunction "4_4") (pintype "passive"))
      (node (ref "P4") (pin "4") (pinfunction "4_4") (pintype "passive"))
      (node (ref "P5") (pin "4") (pinfunction "4_4") (pintype "passive"))
      (node (ref "R27") (pin "1") (pinfunction "1_1") (pintype "passive"))
      (node (ref "TP10") (pin "1") (pinfunction "1_1") (pintype "passive"))
      (node (ref "U1") (pin "93") (pinfunction "PB7_93") (pintype "bidirectional"))
      (node (ref "U8") (pin "4") (pinfunction "SDA_4") (pintype "bidirectional"))
    )
    (net (code "35") (name "/SDI") (class "Default")
      (node (ref "U1") (pin "54") (pinfunction "PB15_54") (pintype "bidirectional"))
      (node (ref "U2") (pin "14") (pinfunction "AP_SDA/AP_SDIO/AP_SDI_14") (pintype "bidirectional"))
    )
    (net (code "36") (name "/SDO") (class "Default")
      (node (ref "U1") (pin "53") (pinfunction "PB14_53") (pintype "bidirectional"))
      (node (ref "U2") (pin "1") (pinfunction "AP_SDO/AP_AD0_1") (pintype "bidirectional"))
    )
    (net (code "37") (name "/SWCLK") (class "Default")
      (node (ref "J2") (pin "5") (pinfunction "5_5") (pintype "passive"))
      (node (ref "TP6") (pin "1") (pinfunction "1_1") (pintype "passive"))
      (node (ref "U1") (pin "76") (pinfunction "PA14_76") (pintype "bidirectional"))
    )
    (net (code "38") (name "/SWDIO") (class "Default")
      (node (ref "J2") (pin "3") (pinfunction "3_3") (pintype "passive"))
      (node (ref "TP5") (pin "1") (pinfunction "1_1") (pintype "passive"))
      (node (ref "U1") (pin "72") (pinfunction "PA13_72") (pintype "bidirectional"))
    )
    (net (code "39") (name "/SWITCH") (class "Default")
      (node (ref "S4") (pin "2") (pinfunction "2_2") (pintype "passive"))
      (node (ref "U1") (pin "58") (pinfunction "PD11_58") (pintype "bidirectional"))
    )
    (net (code "40") (name "/SWO") (class "Default")
      (node (ref "J2") (pin "2") (pinfunction "2_2") (pintype "passive"))
      (node (ref "U1") (pin "89") (pinfunction "PB3_89") (pintype "bidirectional"))
    )
    (net (code "41") (name "/TX") (class "Default")
      (node (ref "J2") (pin "7") (pinfunction "7_7") (pintype "passive"))
      (node (ref "TP7") (pin "1") (pinfunction "1_1") (pintype "passive"))
      (node (ref "U1") (pin "68") (pinfunction "PA9_68") (pintype "bidirectional"))
    )
    (net (code "42") (name "/TX BT") (class "Default")
      (node (ref "U1") (pin "56") (pinfunction "PD9_56") (pintype "bidirectional"))
      (node (ref "U5") (pin "12") (pinfunction "TXD(P0.14)_12") (pintype "bidirectional"))
    )
    (net (code "43") (name "/VCAP1") (class "Default")
      (node (ref "C4") (pin "2") (pinfunction "2_2") (pintype "passive"))
      (node (ref "U1") (pin "48") (pinfunction "VCAP_48") (pintype "power_in"))
    )
    (net (code "44") (name "/VCAP2") (class "Default")
      (node (ref "C5") (pin "2") (pinfunction "2_2") (pintype "passive"))
      (node (ref "U1") (pin "73") (pinfunction "VCAP_73") (pintype "power_in"))
    )
    (net (code "45") (name "/VCP M1") (class "Default")
      (node (ref "C18") (pin "2") (pinfunction "2_2") (pintype "passive"))
      (node (ref "U3") (pin "12") (pinfunction "VCP_12") (pintype "power_in"))
    )
    (net (code "46") (name "/VCP M2") (class "Default")
      (node (ref "C24") (pin "2") (pinfunction "2_2") (pintype "passive"))
      (node (ref "U4") (pin "12") (pinfunction "VCP_12") (pintype "power_in"))
    )
    (net (code "47") (name "/VREF M1") (class "Default")
      (node (ref "C19") (pin "2") (pinfunction "2_2") (pintype "passive"))
      (node (ref "R6") (pin "1") (pinfunction "1_1") (pintype "passive"))
      (node (ref "U3") (pin "5") (pinfunction "VREF_5") (pintype "input"))
    )
    (net (code "48") (name "/VREF M2") (class "Default")
      (node (ref "C20") (pin "2") (pinfunction "2_2") (pintype "passive"))
      (node (ref "R8") (pin "1") (pinfunction "1_1") (pintype "passive"))
      (node (ref "U4") (pin "5") (pinfunction "VREF_5") (pintype "input"))
    )
    (net (code "49") (name "/W{slash}S") (class "Default")
      (node (ref "U1") (pin "63") (pinfunction "PC6_63") (pintype "bidirectional"))
      (node (ref "U5") (pin "7") (pinfunction "WKP(P0.05)_7") (pintype "bidirectional"))
    )
    (net (code "50") (name "/XSHUT1") (class "Default")
      (node (ref "P1") (pin "6") (pinfunction "6_6") (pintype "passive"))
      (node (ref "U1") (pin "97") (pinfunction "PE0_97") (pintype "bidirectional"))
    )
    (net (code "51") (name "/XSHUT2") (class "Default")
      (node (ref "P2") (pin "6") (pinfunction "6_6") (pintype "passive"))
      (node (ref "U1") (pin "98") (pinfunction "PE1_98") (pintype "bidirectional"))
    )
    (net (code "52") (name "/XSHUT3") (class "Default")
      (node (ref "P3") (pin "6") (pinfunction "6_6") (pintype "passive"))
      (node (ref "U1") (pin "1") (pinfunction "PE2_1") (pintype "bidirectional"))
    )
    (net (code "53") (name "/XSHUT4") (class "Default")
      (node (ref "P4") (pin "6") (pinfunction "6_6") (pintype "passive"))
      (node (ref "U1") (pin "3") (pinfunction "PE4_3") (pintype "bidirectional"))
    )
    (net (code "54") (name "/XSHUT5") (class "Default")
      (node (ref "P5") (pin "6") (pinfunction "6_6") (pintype "passive"))
      (node (ref "U1") (pin "4") (pinfunction "PE5_4") (pintype "bidirectional"))
    )
    (net (code "55") (name "3.3V") (class "Default")
      (node (ref "C10") (pin "2") (pinfunction "2_2") (pintype "passive"))
      (node (ref "C11") (pin "1") (pinfunction "1_1") (pintype "passive"))
      (node (ref "C14") (pin "2") (pinfunction "2_2") (pintype "passive"))
      (node (ref "C27") (pin "2") (pinfunction "2_2") (pintype "passive"))
      (node (ref "C29") (pin "2") (pinfunction "2_2") (pintype "passive"))
      (node (ref "C3") (pin "2") (pinfunction "2_2") (pintype "passive"))
      (node (ref "C30") (pin "2") (pinfunction "2_2") (pintype "passive"))
      (node (ref "C6") (pin "2") (pinfunction "2_2") (pintype "passive"))
      (node (ref "C7") (pin "2") (pinfunction "2_2") (pintype "passive"))
      (node (ref "C8") (pin "2") (pinfunction "2_2") (pintype "passive"))
      (node (ref "C9") (pin "2") (pinfunction "2_2") (pintype "passive"))
      (node (ref "FL1") (pin "2") (pinfunction "2_2") (pintype "passive"))
      (node (ref "FL2") (pin "2") (pinfunction "2_2") (pintype "passive"))
      (node (ref "J2") (pin "1") (pinfunction "1_1") (pintype "passive"))
      (node (ref "P1") (pin "1") (pinfunction "1_1") (pintype "passive"))
      (node (ref "P2") (pin "1") (pinfunction "1_1") (pintype "passive"))
      (node (ref "P3") (pin "1") (pinfunction "1_1") (pintype "passive"))
      (node (ref "P4") (pin "1") (pinfunction "1_1") (pintype "passive"))
      (node (ref "P5") (pin "1") (pinfunction "1_1") (pintype "passive"))
      (node (ref "R10") (pin "1") (pinfunction "1_1") (pintype "passive"))
      (node (ref "R11") (pin "1") (pinfunction "1_1") (pintype "passive"))
      (node (ref "R12") (pin "2") (pinfunction "2_2") (pintype "passive"))
      (node (ref "R13") (pin "1") (pinfunction "1_1") (pintype "passive"))
      (node (ref "R14") (pin "1") (pinfunction "1_1") (pintype "passive"))
      (node (ref "R15") (pin "1") (pinfunction "1_1") (pintype "passive"))
      (node (ref "R17") (pin "2") (pinfunction "2_2") (pintype "passive"))
      (node (ref "R19") (pin "2") (pinfunction "2_2") (pintype "passive"))
      (node (ref "R2") (pin "2") (pinfunction "2_2") (pintype "passive"))
      (node (ref "R21") (pin "2") (pinfunction "2_2") (pintype "passive"))
      (node (ref "R22") (pin "2") (pinfunction "2_2") (pintype "passive"))
      (node (ref "R27") (pin "2") (pinfunction "2_2") (pintype "passive"))
      (node (ref "R28") (pin "2") (pinfunction "2_2") (pintype "passive"))
      (node (ref "R5") (pin "1") (pinfunction "1_1") (pintype "passive"))
      (node (ref "R7") (pin "1") (pinfunction "1_1") (pintype "passive"))
      (node (ref "S1") (pin "2") (pinfunction "2_2") (pintype "passive"))
      (node (ref "TP1") (pin "1") (pinfunction "1_1") (pintype "passive"))
      (node (ref "U1") (pin "100") (pinfunction "VDD_100") (pintype "power_in"))
      (node (ref "U1") (pin "11") (pinfunction "VDD_11") (pintype "power_in"))
      (node (ref "U1") (pin "27") (pinfunction "VDD_27") (pintype "power_in"))
      (node (ref "U1") (pin "50") (pinfunction "VDD_50") (pintype "power_in"))
      (node (ref "U1") (pin "6") (pinfunction "VBAT_6") (pintype "power_in"))
      (node (ref "U1") (pin "75") (pinfunction "VDD_75") (pintype "power_in"))
      (node (ref "U12") (pin "4") (pinfunction "VOUT_4") (pintype "output"))
      (node (ref "U2") (pin "5") (pinfunction "VDDIO_5") (pintype "power_in"))
      (node (ref "U5") (pin "4") (pinfunction "VCC_4") (pintype "power_in"))
      (node (ref "U8") (pin "2") (pinfunction "VCC_IN_2") (pintype "power_in"))
    )
    (net (code "56") (name "7.4V") (class "Default")
      (node (ref "C13") (pin "2") (pinfunction "2_2") (pintype "passive"))
      (node (ref "C16") (pin "2") (pinfunction "2_2") (pintype "passive"))
      (node (ref "C17") (pin "1") (pinfunction "1_1") (pintype "passive"))
      (node (ref "C22") (pin "2") (pinfunction "2_2") (pintype "passive"))
      (node (ref "C23") (pin "1") (pinfunction "1_1") (pintype "passive"))
      (node (ref "C32") (pin "2") (pinfunction "2_2") (pintype "passive"))
      (node (ref "TP3") (pin "1") (pinfunction "1_1") (pintype "passive"))
      (node (ref "U12") (pin "1") (pinfunction "EN_1") (pintype "input"))
      (node (ref "U12") (pin "2") (pinfunction "VIN_2") (pintype "input"))
      (node (ref "U3") (pin "11") (pinfunction "VM_11") (pintype "power_in"))
      (node (ref "U4") (pin "11") (pinfunction "VM_11") (pintype "power_in"))
      (node (ref "U9") (pin "3") (pinfunction "D_3") (pintype "passive"))
    )
    (net (code "57") (name "7.4V BAT") (class "Default")
      (node (ref "S2") (pin "1") (pinfunction "COM_1") (pintype "passive"))
      (node (ref "U9") (pin "2") (pinfunction "S_2") (pintype "passive"))
    )
    (net (code "58") (name "BAT") (class "Default")
      (node (ref "J1") (pin "1") (pinfunction "1_1") (pintype "passive"))
      (node (ref "S2") (pin "2") (pinfunction "NO_2") (pintype "passive"))
    )
    (net (code "59") (name "GND") (class "Default")
      (node (ref "C1") (pin "2") (pinfunction "2_2") (pintype "passive"))
      (node (ref "C10") (pin "1") (pinfunction "1_1") (pintype "passive"))
      (node (ref "C11") (pin "2") (pinfunction "2_2") (pintype "passive"))
      (node (ref "C12") (pin "1") (pinfunction "1_1") (pintype "passive"))
      (node (ref "C13") (pin "1") (pinfunction "1_1") (pintype "passive"))
      (node (ref "C14") (pin "1") (pinfunction "1_1") (pintype "passive"))
      (node (ref "C16") (pin "1") (pinfunction "1_1") (pintype "passive"))
      (node (ref "C17") (pin "2") (pinfunction "2_2") (pintype "passive"))
      (node (ref "C19") (pin "1") (pinfunction "1_1") (pintype "passive"))
      (node (ref "C2") (pin "2") (pinfunction "2_2") (pintype "passive"))
      (node (ref "C20") (pin "1") (pinfunction "1_1") (pintype "passive"))
      (node (ref "C22") (pin "1") (pinfunction "1_1") (pintype "passive"))
      (node (ref "C23") (pin "2") (pinfunction "2_2") (pintype "passive"))
      (node (ref "C25") (pin "1") (pinfunction "1_1") (pintype "passive"))
      (node (ref "C26") (pin "1") (pinfunction "1_1") (pintype "passive"))
      (node (ref "C27") (pin "1") (pinfunction "1_1") (pintype "passive"))
      (node (ref "C28") (pin "2") (pinfunction "2_2") (pintype "passive"))
      (node (ref "C29") (pin "1") (pinfunction "1_1") (pintype "passive"))
      (node (ref "C3") (pin "1") (pinfunction "1_1") (pintype "passive"))
      (node (ref "C30") (pin "1") (pinfunction "1_1") (pintype "passive"))
      (node (ref "C31") (pin "1") (pinfunction "1_1") (pintype "passive"))
      (node (ref "C32") (pin "1") (pinfunction "1_1") (pintype "passive"))
      (node (ref "C4") (pin "1") (pinfunction "1_1") (pintype "passive"))
      (node (ref "C5") (pin "1") (pinfunction "1_1") (pintype "passive"))
      (node (ref "C6") (pin "1") (pinfunction "1_1") (pintype "passive"))
      (node (ref "C7") (pin "1") (pinfunction "1_1") (pintype "passive"))
      (node (ref "C8") (pin "1") (pinfunction "1_1") (pintype "passive"))
      (node (ref "C9") (pin "1") (pinfunction "1_1") (pintype "passive"))
      (node (ref "D2") (pin "C") (pinfunction "C_C") (pintype "passive"))
      (node (ref "D3") (pin "C") (pinfunction "C_C") (pintype "passive"))
      (node (ref "D4") (pin "C") (pinfunction "C_C") (pintype "passive"))
      (node (ref "D5") (pin "C") (pinfunction "C_C") (pintype "passive"))
      (node (ref "D6") (pin "C") (pinfunction "C_C") (pintype "passive"))
      (node (ref "D7") (pin "C") (pinfunction "C_C") (pintype "passive"))
      (node (ref "D8") (pin "C") (pinfunction "C_C") (pintype "passive"))
      (node (ref "J1") (pin "2") (pinfunction "2_2") (pintype "passive"))
      (node (ref "J2") (pin "10") (pinfunction "10_10") (pintype "passive"))
      (node (ref "J2") (pin "6") (pinfunction "6_6") (pintype "passive"))
      (node (ref "J2") (pin "8") (pinfunction "8_8") (pintype "passive"))
      (node (ref "P1") (pin "2") (pinfunction "2_2") (pintype "passive"))
      (node (ref "P2") (pin "2") (pinfunction "2_2") (pintype "passive"))
      (node (ref "P3") (pin "2") (pinfunction "2_2") (pintype "passive"))
      (node (ref "P4") (pin "2") (pinfunction "2_2") (pintype "passive"))
      (node (ref "P5") (pin "2") (pinfunction "2_2") (pintype "passive"))
      (node (ref "Q1") (pin "E") (pinfunction "E_E") (pintype "passive"))
      (node (ref "Q2") (pin "E") (pinfunction "E_E") (pintype "passive"))
      (node (ref "Q3") (pin "E") (pinfunction "E_E") (pintype "passive"))
      (node (ref "R1") (pin "1") (pinfunction "1_1") (pintype "passive"))
      (node (ref "R26") (pin "2") (pinfunction "2_2") (pintype "passive"))
      (node (ref "R3") (pin "1") (pinfunction "1_1") (pintype "passive"))
      (node (ref "R4") (pin "1") (pinfunction "1_1") (pintype "passive"))
      (node (ref "R9") (pin "1") (pinfunction "1_1") (pintype "passive"))
      (node (ref "S3") (pin "1") (pinfunction "1_1") (pintype "passive"))
      (node (ref "S4") (pin "1") (pinfunction "1_1") (pintype "passive"))
      (node (ref "TP2") (pin "1") (pinfunction "1_1") (pintype "passive"))
      (node (ref "U1") (pin "10") (pinfunction "VSS_10") (pintype "power_in"))
      (node (ref "U1") (pin "19") (pinfunction "VSSA_19") (pintype "power_in"))
      (node (ref "U1") (pin "26") (pinfunction "VSS_26") (pintype "power_in"))
      (node (ref "U1") (pin "49") (pinfunction "VSS_49") (pintype "power_in"))
      (node (ref "U1") (pin "74") (pinfunction "VSS_74") (pintype "power_in"))
      (node (ref "U1") (pin "99") (pinfunction "VSS_99") (pintype "power_in"))
      (node (ref "U12") (pin "10") (pinfunction "GND_10") (pintype "power_in"))
      (node (ref "U12") (pin "11") (pinfunction "GND_11") (pintype "power_in"))
      (node (ref "U12") (pin "12") (pinfunction "GND_12") (pintype "power_in"))
      (node (ref "U12") (pin "3") (pinfunction "GND_3") (pintype "power_in"))
      (node (ref "U12") (pin "9") (pinfunction "GND_9") (pintype "power_in"))
      (node (ref "U2") (pin "10") (pinfunction "RESV_10_10") (pintype "passive"))
      (node (ref "U2") (pin "11") (pinfunction "RESV_11_11") (pintype "passive"))
      (node (ref "U2") (pin "2") (pinfunction "RESV_2_2") (pintype "passive"))
      (node (ref "U2") (pin "3") (pinfunction "RESV_3_3") (pintype "passive"))
      (node (ref "U2") (pin "6") (pinfunction "GND_6") (pintype "power_in"))
      (node (ref "U2") (pin "7") (pinfunction "RESV_7_7") (pintype "passive"))
      (node (ref "U2") (pin "9") (pinfunction "INT2/FSYNC/CLKIN_9") (pintype "bidirectional"))
      (node (ref "U3") (pin "15") (pinfunction "GND_15") (pintype "power_in"))
      (node (ref "U3") (pin "16") (pinfunction "PMODE_16") (pintype "input"))
      (node (ref "U3") (pin "7") (pinfunction "IMODE_7") (pintype "input"))
      (node (ref "U3") (pin "9") (pinfunction "PGND_9") (pintype "power_in"))
      (node (ref "U4") (pin "15") (pinfunction "GND_15") (pintype "power_in"))
      (node (ref "U4") (pin "16") (pinfunction "PMODE_16") (pintype "input"))
      (node (ref "U4") (pin "7") (pinfunction "IMODE_7") (pintype "input"))
      (node (ref "U4") (pin "9") (pinfunction "PGND_9") (pintype "power_in"))
      (node (ref "U5") (pin "14") (pinfunction "GND_14") (pintype "power_in"))
      (node (ref "U5") (pin "5") (pinfunction "GND_5") (pintype "power_in"))
      (node (ref "U6") (pin "2") (pinfunction "C_2") (pintype "passive"))
      (node (ref "U6") (pin "4") (pinfunction "ET_4") (pintype "passive"))
      (node (ref "U7") (pin "2") (pinfunction "C_2") (pintype "passive"))
      (node (ref "U7") (pin "4") (pinfunction "ET_4") (pintype "passive"))
      (node (ref "U8") (pin "1") (pinfunction "GND_1") (pintype "power_in"))
    )
    (net (code "60") (name "Net-(D2-PadA)") (class "Default")
      (node (ref "D2") (pin "A") (pinfunction "A_A") (pintype "passive"))
      (node (ref "R16") (pin "1") (pinfunction "1_1") (pintype "passive"))
    )
    (net (code "61") (name "Net-(D3-PadA)") (class "Default")
      (node (ref "D3") (pin "A") (pinfunction "A_A") (pintype "passive"))
      (node (ref "R18") (pin "1") (pinfunction "1_1") (pintype "passive"))
    )
    (net (code "62") (name "Net-(D4-PadA)") (class "Default")
      (node (ref "D4") (pin "A") (pinfunction "A_A") (pintype "passive"))
      (node (ref "R20") (pin "1") (pinfunction "1_1") (pintype "passive"))
    )
    (net (code "63") (name "Net-(M1-+)") (class "Default")
      (node (ref "M1") (pin "1") (pinfunction "+_1") (pintype "passive"))
      (node (ref "U3") (pin "8") (pinfunction "OUT1_8") (pintype "output"))
    )
    (net (code "64") (name "Net-(M1--)") (class "Default")
      (node (ref "M1") (pin "2") (pinfunction "-_2") (pintype "passive"))
      (node (ref "U3") (pin "10") (pinfunction "OUT2_10") (pintype "output"))
    )
    (net (code "65") (name "Net-(M2-+)") (class "Default")
      (node (ref "M2") (pin "1") (pinfunction "+_1") (pintype "passive"))
      (node (ref "U4") (pin "8") (pinfunction "OUT1_8") (pintype "output"))
    )
    (net (code "66") (name "Net-(M2--)") (class "Default")
      (node (ref "M2") (pin "2") (pinfunction "-_2") (pintype "passive"))
      (node (ref "U4") (pin "10") (pinfunction "OUT2_10") (pintype "output"))
    )
    (net (code "67") (name "Net-(U1-VDDA)") (class "Default")
      (node (ref "C1") (pin "1") (pinfunction "1_1") (pintype "passive"))
      (node (ref "C2") (pin "1") (pinfunction "1_1") (pintype "passive"))
      (node (ref "FL1") (pin "1") (pinfunction "1_1") (pintype "passive"))
      (node (ref "U1") (pin "20") (pinfunction "VREF+_20") (pintype "power_in"))
      (node (ref "U1") (pin "21") (pinfunction "VDDA_21") (pintype "power_in"))
    )
    (net (code "68") (name "Net-(U2-VDD)") (class "Default")
      (node (ref "C25") (pin "2") (pinfunction "2_2") (pintype "passive"))
      (node (ref "C26") (pin "2") (pinfunction "2_2") (pintype "passive"))
      (node (ref "FL2") (pin "1") (pinfunction "1_1") (pintype "passive"))
      (node (ref "U2") (pin "8") (pinfunction "VDD_8") (pintype "power_in"))
    )
    (net (code "69") (name "Net-(U3-CPH)") (class "Default")
      (node (ref "C15") (pin "2") (pinfunction "2_2") (pintype "passive"))
      (node (ref "U3") (pin "13") (pinfunction "CPH_13") (pintype "power_in"))
    )
    (net (code "70") (name "Net-(U3-CPL)") (class "Default")
      (node (ref "C15") (pin "1") (pinfunction "1_1") (pintype "passive"))
      (node (ref "U3") (pin "14") (pinfunction "CPL_14") (pintype "power_in"))
    )
    (net (code "71") (name "Net-(U4-CPH)") (class "Default")
      (node (ref "C21") (pin "2") (pinfunction "2_2") (pintype "passive"))
      (node (ref "U4") (pin "13") (pinfunction "CPH_13") (pintype "power_in"))
    )
    (net (code "72") (name "Net-(U4-CPL)") (class "Default")
      (node (ref "C21") (pin "1") (pinfunction "1_1") (pintype "passive"))
      (node (ref "U4") (pin "14") (pinfunction "CPL_14") (pintype "power_in"))
    )
    (net (code "73") (name "Net-(U5-LINK(P0.16))") (class "Default")
      (node (ref "D1") (pin "C") (pinfunction "C_C") (pintype "passive"))
      (node (ref "U5") (pin "13") (pinfunction "LINK(P0.16)_13") (pintype "bidirectional"))
    )
    (net (code "74") (name "Net-(U6-A)") (class "Default")
      (node (ref "R14") (pin "2") (pinfunction "2_2") (pintype "passive"))
      (node (ref "U6") (pin "1") (pinfunction "A_1") (pintype "passive"))
    )
    (net (code "75") (name "Net-(U7-A)") (class "Default")
      (node (ref "R11") (pin "2") (pinfunction "2_2") (pintype "passive"))
      (node (ref "U7") (pin "1") (pinfunction "A_1") (pintype "passive"))
    )
    (net (code "76") (name "Net-(U9-G)") (class "Default")
      (node (ref "R26") (pin "1") (pinfunction "1_1") (pintype "passive"))
      (node (ref "U9") (pin "1") (pinfunction "G_1") (pintype "passive"))
    )
    (net (code "77") (name "Net-(U12-SS{slash}TR)") (class "Default")
      (node (ref "C12") (pin "2") (pinfunction "2_2") (pintype "passive"))
      (node (ref "U12") (pin "8") (pinfunction "SS/TR_8") (pintype "input"))
    )
    (net (code "78") (name "unconnected-(C18-Pad1)") (class "Default")
      (node (ref "C18") (pin "1") (pinfunction "1_1") (pintype "passive"))
    )
    (net (code "79") (name "unconnected-(C24-Pad1)") (class "Default")
      (node (ref "C24") (pin "1") (pinfunction "1_1") (pintype "passive"))
    )
    (net (code "80") (name "unconnected-(D1-PadA)") (class "Default")
      (node (ref "D1") (pin "A") (pinfunction "A_A") (pintype "passive"))
    )
    (net (code "81") (name "unconnected-(D5-PadA)") (class "Default")
      (node (ref "D5") (pin "A") (pinfunction "A_A") (pintype "passive"))
    )
    (net (code "82") (name "unconnected-(D6-PadA)") (class "Default")
      (node (ref "D6") (pin "A") (pinfunction "A_A") (pintype "passive"))
    )
    (net (code "83") (name "unconnected-(D7-PadA)") (class "Default")
      (node (ref "D7") (pin "A") (pinfunction "A_A") (pintype "passive"))
    )
    (net (code "84") (name "unconnected-(D8-PadA)") (class "Default")
      (node (ref "D8") (pin "A") (pinfunction "A_A") (pintype "passive"))
    )
    (net (code "85") (name "unconnected-(P1-Pad5)") (class "Default")
      (node (ref "P1") (pin "5") (pinfunction "5_5") (pintype "passive+no_connect"))
    )
    (net (code "86") (name "unconnected-(P2-Pad5)") (class "Default")
      (node (ref "P2") (pin "5") (pinfunction "5_5") (pintype "passive+no_connect"))
    )
    (net (code "87") (name "unconnected-(P3-Pad5)") (class "Default")
      (node (ref "P3") (pin "5") (pinfunction "5_5") (pintype "passive+no_connect"))
    )
    (net (code "88") (name "unconnected-(P4-Pad5)") (class "Default")
      (node (ref "P4") (pin "5") (pinfunction "5_5") (pintype "passive+no_connect"))
    )
    (net (code "89") (name "unconnected-(P5-Pad5)") (class "Default")
      (node (ref "P5") (pin "5") (pinfunction "5_5") (pintype "passive+no_connect"))
    )
    (net (code "90") (name "unconnected-(R12-Pad1)") (class "Default")
      (node (ref "R12") (pin "1") (pinfunction "1_1") (pintype "passive"))
    )
    (net (code "91") (name "unconnected-(R22-Pad1)") (class "Default")
      (node (ref "R22") (pin "1") (pinfunction "1_1") (pintype "passive"))
    )
    (net (code "92") (name "unconnected-(R23-Pad1)") (class "Default")
      (node (ref "R23") (pin "1") (pinfunction "1_1") (pintype "passive"))
    )
    (net (code "93") (name "unconnected-(R24-Pad1)") (class "Default")
      (node (ref "R24") (pin "1") (pinfunction "1_1") (pintype "passive"))
    )
    (net (code "94") (name "unconnected-(R25-Pad1)") (class "Default")
      (node (ref "R25") (pin "1") (pinfunction "1_1") (pintype "passive"))
    )
    (net (code "95") (name "unconnected-(U1-PA3-Pad25)") (class "Default")
      (node (ref "U1") (pin "25") (pinfunction "PA3_25") (pintype "bidirectional"))
    )
    (net (code "96") (name "unconnected-(U1-PA6-Pad30)") (class "Default")
      (node (ref "U1") (pin "30") (pinfunction "PA6_30") (pintype "bidirectional"))
    )
    (net (code "97") (name "unconnected-(U1-PA7-Pad31)") (class "Default")
      (node (ref "U1") (pin "31") (pinfunction "PA7_31") (pintype "bidirectional"))
    )
    (net (code "98") (name "unconnected-(U1-PA8-Pad67)") (class "Default")
      (node (ref "U1") (pin "67") (pinfunction "PA8_67") (pintype "bidirectional"))
    )
    (net (code "99") (name "unconnected-(U1-PA11-Pad70)") (class "Default")
      (node (ref "U1") (pin "70") (pinfunction "PA11_70") (pintype "bidirectional"))
    )
    (net (code "100") (name "unconnected-(U1-PA12-Pad71)") (class "Default")
      (node (ref "U1") (pin "71") (pinfunction "PA12_71") (pintype "bidirectional"))
    )
    (net (code "101") (name "unconnected-(U1-PA15-Pad77)") (class "Default")
      (node (ref "U1") (pin "77") (pinfunction "PA15_77") (pintype "bidirectional"))
    )
    (net (code "102") (name "unconnected-(U1-PB0-Pad34)") (class "Default")
      (node (ref "U1") (pin "34") (pinfunction "PB0_34") (pintype "bidirectional"))
    )
    (net (code "103") (name "unconnected-(U1-PB1-Pad35)") (class "Default")
      (node (ref "U1") (pin "35") (pinfunction "PB1_35") (pintype "bidirectional"))
    )
    (net (code "104") (name "unconnected-(U1-PB2-Pad36)") (class "Default")
      (node (ref "U1") (pin "36") (pinfunction "PB2_36") (pintype "bidirectional"))
    )
    (net (code "105") (name "unconnected-(U1-PB4-Pad90)") (class "Default")
      (node (ref "U1") (pin "90") (pinfunction "PB4_90") (pintype "bidirectional"))
    )
    (net (code "106") (name "unconnected-(U1-PB5-Pad91)") (class "Default")
      (node (ref "U1") (pin "91") (pinfunction "PB5_91") (pintype "bidirectional"))
    )
    (net (code "107") (name "unconnected-(U1-PB9-Pad96)") (class "Default")
      (node (ref "U1") (pin "96") (pinfunction "PB9_96") (pintype "bidirectional"))
    )
    (net (code "108") (name "unconnected-(U1-PB10-Pad46)") (class "Default")
      (node (ref "U1") (pin "46") (pinfunction "PB10_46") (pintype "bidirectional"))
    )
    (net (code "109") (name "unconnected-(U1-PB11-Pad47)") (class "Default")
      (node (ref "U1") (pin "47") (pinfunction "PB11_47") (pintype "bidirectional"))
    )
    (net (code "110") (name "unconnected-(U1-PB12-Pad51)") (class "Default")
      (node (ref "U1") (pin "51") (pinfunction "PB12_51") (pintype "bidirectional"))
    )
    (net (code "111") (name "unconnected-(U1-PC2_C-Pad17)") (class "Default")
      (node (ref "U1") (pin "17") (pinfunction "PC2_C_17") (pintype "bidirectional"))
    )
    (net (code "112") (name "unconnected-(U1-PC3_C-Pad18)") (class "Default")
      (node (ref "U1") (pin "18") (pinfunction "PC3_C_18") (pintype "bidirectional"))
    )
    (net (code "113") (name "unconnected-(U1-PC10-Pad78)") (class "Default")
      (node (ref "U1") (pin "78") (pinfunction "PC10_78") (pintype "bidirectional"))
    )
    (net (code "114") (name "unconnected-(U1-PC11-Pad79)") (class "Default")
      (node (ref "U1") (pin "79") (pinfunction "PC11_79") (pintype "bidirectional"))
    )
    (net (code "115") (name "unconnected-(U1-PC12-Pad80)") (class "Default")
      (node (ref "U1") (pin "80") (pinfunction "PC12_80") (pintype "bidirectional"))
    )
    (net (code "116") (name "unconnected-(U1-PC13-Pad7)") (class "Default")
      (node (ref "U1") (pin "7") (pinfunction "PC13_7") (pintype "bidirectional"))
    )
    (net (code "117") (name "unconnected-(U1-PC14-OSC32_IN-Pad8)") (class "Default")
      (node (ref "U1") (pin "8") (pinfunction "PC14-OSC32_IN_8") (pintype "bidirectional"))
    )
    (net (code "118") (name "unconnected-(U1-PC15-OSC32_OUT-Pad9)") (class "Default")
      (node (ref "U1") (pin "9") (pinfunction "PC15-OSC32_OUT_9") (pintype "bidirectional"))
    )
    (net (code "119") (name "unconnected-(U1-PD3-Pad84)") (class "Default")
      (node (ref "U1") (pin "84") (pinfunction "PD3_84") (pintype "bidirectional"))
    )
    (net (code "120") (name "unconnected-(U1-PD4-Pad85)") (class "Default")
      (node (ref "U1") (pin "85") (pinfunction "PD4_85") (pintype "bidirectional"))
    )
    (net (code "121") (name "unconnected-(U1-PD5-Pad86)") (class "Default")
      (node (ref "U1") (pin "86") (pinfunction "PD5_86") (pintype "bidirectional"))
    )
    (net (code "122") (name "unconnected-(U1-PD7-Pad88)") (class "Default")
      (node (ref "U1") (pin "88") (pinfunction "PD7_88") (pintype "bidirectional"))
    )
    (net (code "123") (name "unconnected-(U1-PD10-Pad57)") (class "Default")
      (node (ref "U1") (pin "57") (pinfunction "PD10_57") (pintype "bidirectional"))
    )
    (net (code "124") (name "unconnected-(U1-PD15-Pad62)") (class "Default")
      (node (ref "U1") (pin "62") (pinfunction "PD15_62") (pintype "bidirectional"))
    )
    (net (code "125") (name "unconnected-(U1-PE6-Pad5)") (class "Default")
      (node (ref "U1") (pin "5") (pinfunction "PE6_5") (pintype "bidirectional"))
    )
    (net (code "126") (name "unconnected-(U1-PE7-Pad37)") (class "Default")
      (node (ref "U1") (pin "37") (pinfunction "PE7_37") (pintype "bidirectional"))
    )
    (net (code "127") (name "unconnected-(U1-PE8-Pad38)") (class "Default")
      (node (ref "U1") (pin "38") (pinfunction "PE8_38") (pintype "bidirectional"))
    )
    (net (code "128") (name "unconnected-(U1-PE14-Pad44)") (class "Default")
      (node (ref "U1") (pin "44") (pinfunction "PE14_44") (pintype "bidirectional"))
    )
    (net (code "129") (name "unconnected-(U1-PE15-Pad45)") (class "Default")
      (node (ref "U1") (pin "45") (pinfunction "PE15_45") (pintype "bidirectional"))
    )
    (net (code "130") (name "unconnected-(U1-PH0-OSC_IN-Pad12)") (class "Default")
      (node (ref "U1") (pin "12") (pinfunction "PH0-OSC_IN_12") (pintype "bidirectional"))
    )
    (net (code "131") (name "unconnected-(U1-PH1-OSC_OUT-Pad13)") (class "Default")
      (node (ref "U1") (pin "13") (pinfunction "PH1-OSC_OUT_13") (pintype "bidirectional"))
    )
    (net (code "132") (name "unconnected-(U5-P0.00-Pad8)") (class "Default")
      (node (ref "U5") (pin "8") (pinfunction "P0.00_8") (pintype "bidirectional+no_connect"))
    )
    (net (code "133") (name "unconnected-(U5-P0.01-Pad10)") (class "Default")
      (node (ref "U5") (pin "10") (pinfunction "P0.01_10") (pintype "bidirectional+no_connect"))
    )
    (net (code "134") (name "unconnected-(U5-SWCLK-Pad2)") (class "Default")
      (node (ref "U5") (pin "2") (pinfunction "SWCLK_2") (pintype "bidirectional+no_connect"))
    )
    (net (code "135") (name "unconnected-(U5-SWDIO-Pad1)") (class "Default")
      (node (ref "U5") (pin "1") (pinfunction "SWDIO_1") (pintype "bidirectional+no_connect"))
    )
    (net (code "136") (name "unconnected-(U12-PG-Pad7)") (class "Default")
      (node (ref "U12") (pin "7") (pinfunction "PG_7") (pintype "output+no_connect"))
    )
    (net (code "137") (name "unconnected-(U12-VOUT-Pad5)") (class "Default")
      (node (ref "U12") (pin "5") (pinfunction "VOUT_5") (pintype "output+no_connect"))
    )
  )
)
